# Grove-BLE_dual_model_v1_0.net
KiCad netlist of a schematic drawn in EAGLE
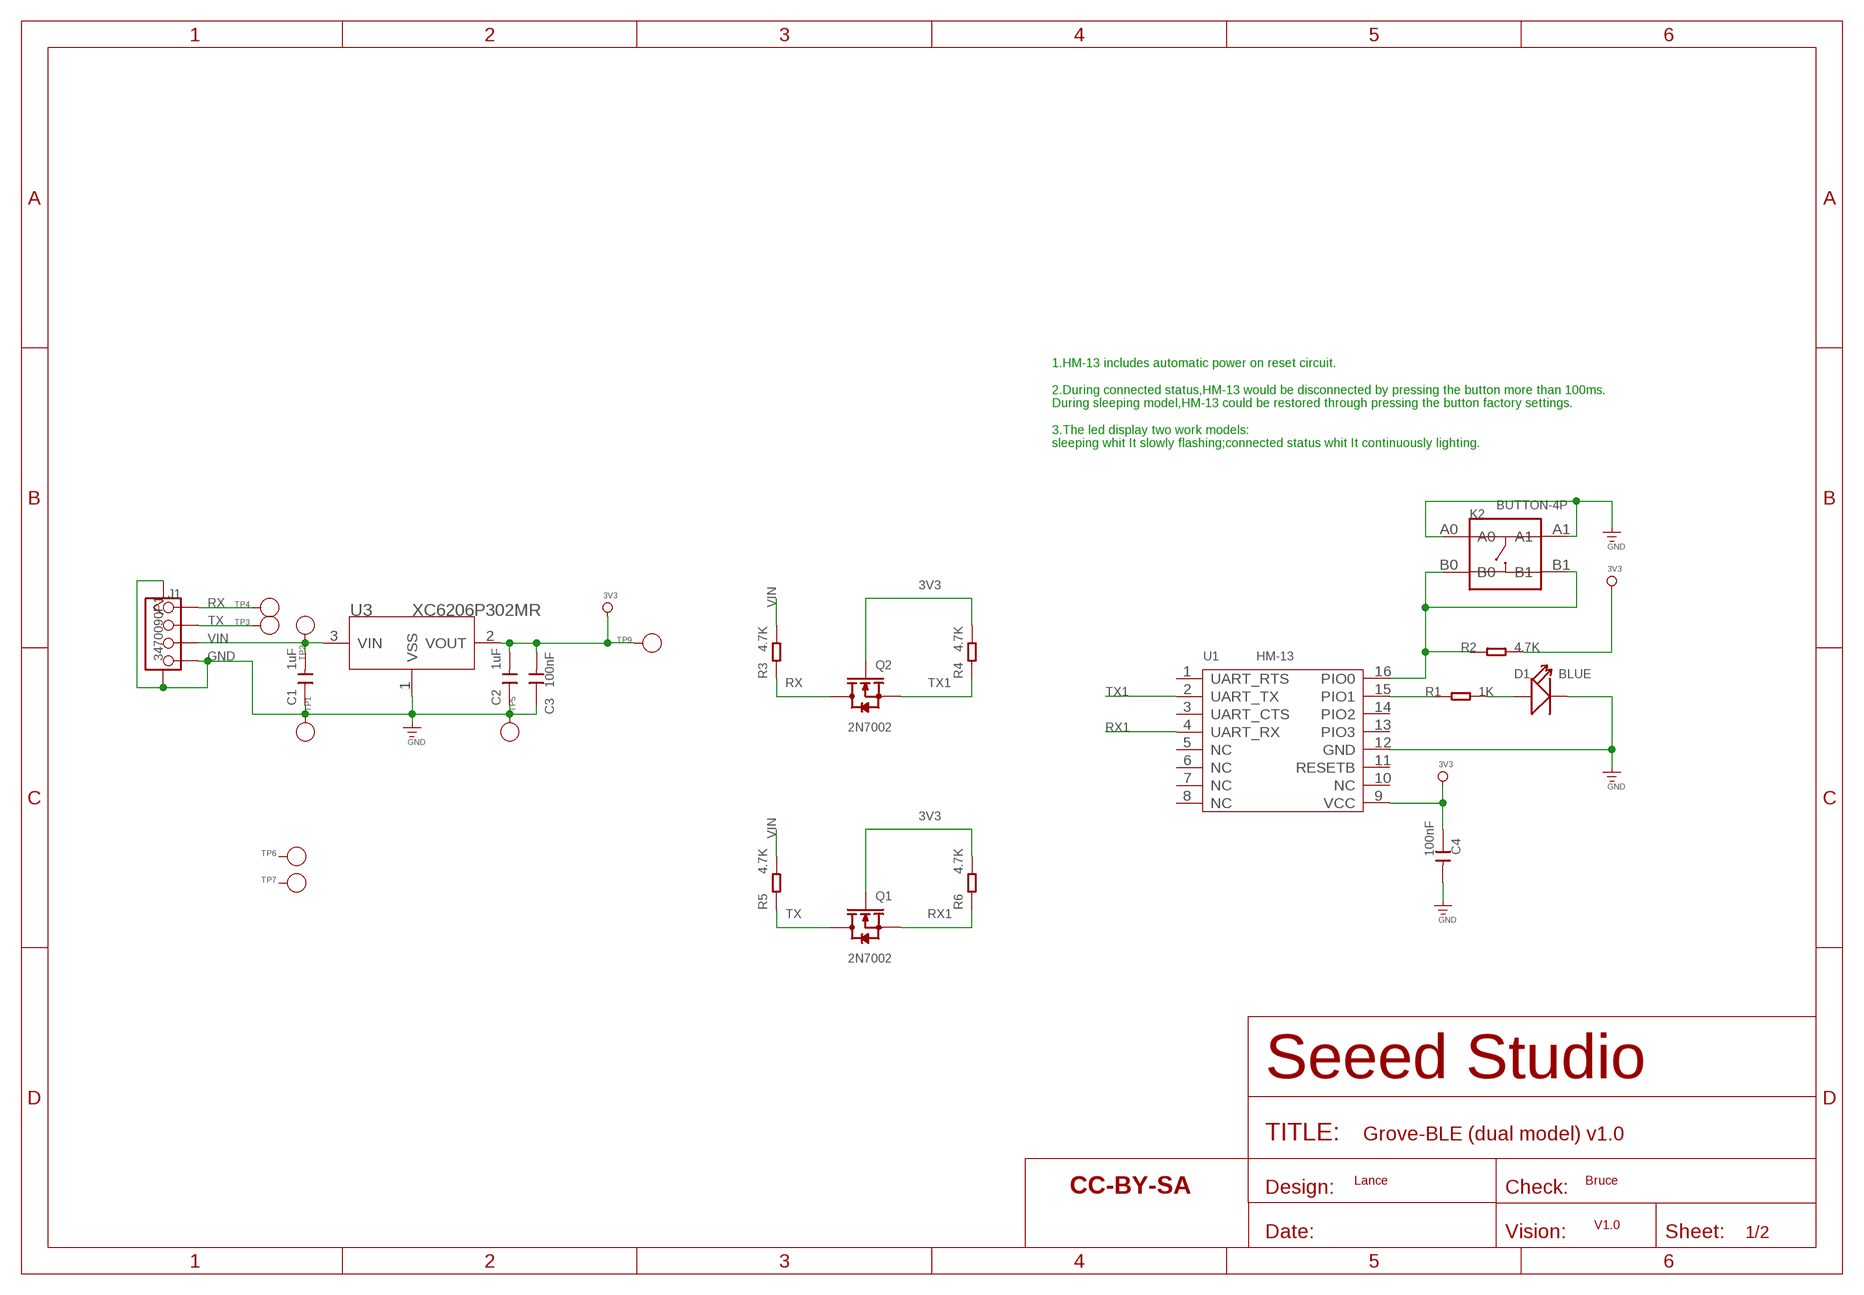
[diagram p0: schematic, sheet 1]
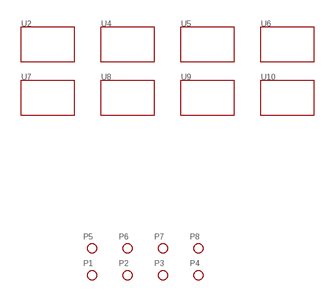
[diagram p1: schematic, sheet 2]

(export (version "E")
  (design (tool "Eeschema 10.0.6"))
  (components
    (comp (ref "C1")
      (value "1uF")
      (footprint "eagle-import:C0603")
      (libsource (lib "eagle-import") (part "C-0603"))
    )
    (comp (ref "C2")
      (value "1uF")
      (footprint "eagle-import:C0603")
      (libsource (lib "eagle-import") (part "C-0603"))
    )
    (comp (ref "C3")
      (value "100nF")
      (footprint "eagle-import:C0603")
      (libsource (lib "eagle-import") (part "C-0603"))
    )
    (comp (ref "C4")
      (value "100nF")
      (footprint "eagle-import:C0603")
      (libsource (lib "eagle-import") (part "C-0603"))
    )
    (comp (ref "D1")
      (value "BLUE")
      (footprint "eagle-import:LED-0603")
      (libsource (lib "eagle-import") (part "LED'0603'"))
    )
    (comp (ref "J1")
      (value "3470090P1")
      (footprint "eagle-import:4P-SMD-2.0")
      (libsource (lib "eagle-import") (part "TWIG-4P-2.0-SMD-FEMALE-REINFORCE'DD'"))
    )
    (comp (ref "K2")
      (value "BUTTON-4P")
      (footprint "eagle-import:4P-SMD-L3.35_W3.35_H1.5MM")
      (libsource (lib "eagle-import") (part "BUTTON-4P-3.3X3.3"))
    )
    (comp (ref "Q1")
      (value "2N7002")
      (footprint "eagle-import:SOT23")
      (libsource (lib "eagle-import") (part "MOSFET-N'SOT23'"))
    )
    (comp (ref "Q2")
      (value "2N7002")
      (footprint "eagle-import:SOT23")
      (libsource (lib "eagle-import") (part "MOSFET-N'SOT23'"))
    )
    (comp (ref "R1")
      (value "1K")
      (footprint "eagle-import:R0603")
      (libsource (lib "eagle-import") (part "R-0603"))
    )
    (comp (ref "R2")
      (value "4.7K")
      (footprint "eagle-import:R0603")
      (libsource (lib "eagle-import") (part "R-0603"))
    )
    (comp (ref "R3")
      (value "4.7K")
      (footprint "eagle-import:R0603")
      (libsource (lib "eagle-import") (part "R-0603"))
    )
    (comp (ref "R4")
      (value "4.7K")
      (footprint "eagle-import:R0603")
      (libsource (lib "eagle-import") (part "R-0603"))
    )
    (comp (ref "R5")
      (value "4.7K")
      (footprint "eagle-import:R0603")
      (libsource (lib "eagle-import") (part "R-0603"))
    )
    (comp (ref "R6")
      (value "4.7K")
      (footprint "eagle-import:R0603")
      (libsource (lib "eagle-import") (part "R-0603"))
    )
    (comp (ref "TP1")
      (value "GND")
      (footprint "eagle-import:TP_4545")
      (fields (field (name "PARTNO") "DNP"))
      (libsource (lib "eagle-import") (part "PAD-TEST-POINT'4545'"))
    )
    (comp (ref "TP2")
      (value "VIN")
      (footprint "eagle-import:TP_4545")
      (fields (field (name "PARTNO") "DNP"))
      (libsource (lib "eagle-import") (part "PAD-TEST-POINT'4545'"))
    )
    (comp (ref "TP3")
      (value "RX")
      (footprint "eagle-import:TP_4545")
      (fields (field (name "PARTNO") "DNP"))
      (libsource (lib "eagle-import") (part "PAD-TEST-POINT'4545'"))
    )
    (comp (ref "TP4")
      (value "TX")
      (footprint "eagle-import:TP_4545")
      (fields (field (name "PARTNO") "DNP"))
      (libsource (lib "eagle-import") (part "PAD-TEST-POINT'4545'"))
    )
    (comp (ref "TP5")
      (value "PAD-TEST-POINT'4545'")
      (footprint "eagle-import:TP_4545")
      (fields (field (name "PARTNO") "DNP"))
      (libsource (lib "eagle-import") (part "PAD-TEST-POINT'4545'"))
    )
    (comp (ref "TP6")
      (value "PAD-TEST-POINT'4545'")
      (footprint "eagle-import:TP_4545")
      (fields (field (name "PARTNO") "DNP"))
      (libsource (lib "eagle-import") (part "PAD-TEST-POINT'4545'"))
    )
    (comp (ref "TP7")
      (value "PAD-TEST-POINT'4545'")
      (footprint "eagle-import:TP_4545")
      (fields (field (name "PARTNO") "DNP"))
      (libsource (lib "eagle-import") (part "PAD-TEST-POINT'4545'"))
    )
    (comp (ref "TP9")
      (value "3V3")
      (footprint "eagle-import:TP_4545")
      (fields (field (name "PARTNO") "DNP"))
      (libsource (lib "eagle-import") (part "PAD-TEST-POINT'4545'"))
    )
    (comp (ref "U$1")
      (value "SEEEDSTUDIO-OPEN-SCH-FRAME")
      (footprint "eagle-import:SEEEDSTUDIO-PCB-FRAME")
      (libsource (lib "eagle-import") (part "SEEEDSTUDIO-OPEN-SCH-FRAME"))
    )
    (comp (ref "U1")
      (value "HM-13")
      (footprint "eagle-import:16P-L18.5_W13.5_H2.3MM")
      (libsource (lib "eagle-import") (part "MOUDLE-BLUETOOTH-HM-13"))
    )
    (comp (ref "U3")
      (value "XC6206P302MR")
      (footprint "eagle-import:SOT23")
      (libsource (lib "eagle-import") (part "XC6206MR"))
    )
    (comp (ref "P1")
      (value "PAD-MARK")
      (footprint "eagle-import:ROUND-MARK-1.0")
      (fields (field (name "PARTNO") "DNP"))
      (libsource (lib "eagle-import") (part "PAD-MARK"))
    )
    (comp (ref "P2")
      (value "PAD-MARK")
      (footprint "eagle-import:ROUND-MARK-1.0")
      (fields (field (name "PARTNO") "DNP"))
      (libsource (lib "eagle-import") (part "PAD-MARK"))
    )
    (comp (ref "P3")
      (value "PAD-MARK")
      (footprint "eagle-import:ROUND-MARK-1.0")
      (fields (field (name "PARTNO") "DNP"))
      (libsource (lib "eagle-import") (part "PAD-MARK"))
    )
    (comp (ref "P4")
      (value "PAD-MARK")
      (footprint "eagle-import:ROUND-MARK-1.0")
      (fields (field (name "PARTNO") "DNP"))
      (libsource (lib "eagle-import") (part "PAD-MARK"))
    )
    (comp (ref "P5")
      (value "PAD-MARK")
      (footprint "eagle-import:ROUND-MARK-1.0")
      (fields (field (name "PARTNO") "DNP"))
      (libsource (lib "eagle-import") (part "PAD-MARK"))
    )
    (comp (ref "P6")
      (value "PAD-MARK")
      (footprint "eagle-import:ROUND-MARK-1.0")
      (fields (field (name "PARTNO") "DNP"))
      (libsource (lib "eagle-import") (part "PAD-MARK"))
    )
    (comp (ref "P7")
      (value "PAD-MARK")
      (footprint "eagle-import:ROUND-MARK-1.0")
      (fields (field (name "PARTNO") "DNP"))
      (libsource (lib "eagle-import") (part "PAD-MARK"))
    )
    (comp (ref "P8")
      (value "PAD-MARK")
      (footprint "eagle-import:ROUND-MARK-1.0")
      (fields (field (name "PARTNO") "DNP"))
      (libsource (lib "eagle-import") (part "PAD-MARK"))
    )
    (comp (ref "U2")
      (value "TWIG'2U'")
      (footprint "eagle-import:GROVE-TEST-PLATFORM")
      (libsource (lib "eagle-import") (part "TWIG'2U'"))
    )
    (comp (ref "U4")
      (value "TWIG'2U'")
      (footprint "eagle-import:GROVE-TEST-PLATFORM")
      (libsource (lib "eagle-import") (part "TWIG'2U'"))
    )
    (comp (ref "U5")
      (value "TWIG'2U'")
      (footprint "eagle-import:GROVE-TEST-PLATFORM")
      (libsource (lib "eagle-import") (part "TWIG'2U'"))
    )
    (comp (ref "U6")
      (value "TWIG'2U'")
      (footprint "eagle-import:GROVE-TEST-PLATFORM")
      (libsource (lib "eagle-import") (part "TWIG'2U'"))
    )
    (comp (ref "U7")
      (value "TWIG'2U'")
      (footprint "eagle-import:GROVE-TEST-PLATFORM")
      (libsource (lib "eagle-import") (part "TWIG'2U'"))
    )
    (comp (ref "U8")
      (value "TWIG'2U'")
      (footprint "eagle-import:GROVE-TEST-PLATFORM")
      (libsource (lib "eagle-import") (part "TWIG'2U'"))
    )
    (comp (ref "U9")
      (value "TWIG'2U'")
      (footprint "eagle-import:GROVE-TEST-PLATFORM")
      (libsource (lib "eagle-import") (part "TWIG'2U'"))
    )
    (comp (ref "U10")
      (value "TWIG'2U'")
      (footprint "eagle-import:GROVE-TEST-PLATFORM")
      (libsource (lib "eagle-import") (part "TWIG'2U'"))
    )
  )
  (nets
    (net (code "1") (name "3V3") (class "Default")
      (node (ref "C2") (pin "2") (pinfunction "2_2") (pintype "passive"))
      (node (ref "C3") (pin "2") (pinfunction "2_2") (pintype "passive"))
      (node (ref "C4") (pin "1") (pinfunction "1_1") (pintype "passive"))
      (node (ref "Q1") (pin "1") (pinfunction "G_1") (pintype "passive"))
      (node (ref "Q2") (pin "1") (pinfunction "G_1") (pintype "passive"))
      (node (ref "R2") (pin "2") (pinfunction "2_2") (pintype "passive"))
      (node (ref "R4") (pin "2") (pinfunction "2_2") (pintype "passive"))
      (node (ref "R6") (pin "2") (pinfunction "2_2") (pintype "passive"))
      (node (ref "TP9") (pin "T") (pinfunction "T_T") (pintype "bidirectional"))
      (node (ref "U1") (pin "9") (pinfunction "VCC_9") (pintype "bidirectional"))
      (node (ref "U3") (pin "2") (pinfunction "VOUT_2") (pintype "output"))
    )
    (net (code "2") (name "GND") (class "Default")
      (node (ref "C1") (pin "1") (pinfunction "1_1") (pintype "passive"))
      (node (ref "C2") (pin "1") (pinfunction "1_1") (pintype "passive"))
      (node (ref "C3") (pin "1") (pinfunction "1_1") (pintype "passive"))
      (node (ref "C4") (pin "2") (pinfunction "2_2") (pintype "passive"))
      (node (ref "D1") (pin "-") (pinfunction "-_-") (pintype "passive"))
      (node (ref "J1") (pin "4") (pinfunction "4_4") (pintype "bidirectional"))
      (node (ref "J1") (pin "SS1") (pinfunction "SS1_SS1") (pintype "bidirectional"))
      (node (ref "J1") (pin "SS2") (pinfunction "SS2_SS2") (pintype "bidirectional"))
      (node (ref "K2") (pin "A0") (pinfunction "A0_A0") (pintype "bidirectional"))
      (node (ref "K2") (pin "A1") (pinfunction "A1_A1") (pintype "bidirectional"))
      (node (ref "TP1") (pin "T") (pinfunction "T_T") (pintype "bidirectional"))
      (node (ref "TP5") (pin "T") (pinfunction "T_T") (pintype "bidirectional"))
      (node (ref "U1") (pin "12") (pinfunction "GND_12") (pintype "bidirectional"))
      (node (ref "U3") (pin "1") (pinfunction "VSS_1") (pintype "power_in"))
    )
    (net (code "3") (name "Net-(D1-Pad+)") (class "Default")
      (node (ref "D1") (pin "+") (pinfunction "+_+") (pintype "passive"))
      (node (ref "R1") (pin "2") (pinfunction "2_2") (pintype "passive"))
    )
    (net (code "4") (name "Net-(U1-PIO0)") (class "Default")
      (node (ref "K2") (pin "B0") (pinfunction "B0_B0") (pintype "bidirectional"))
      (node (ref "K2") (pin "B1") (pinfunction "B1_B1") (pintype "bidirectional"))
      (node (ref "R2") (pin "1") (pinfunction "1_1") (pintype "passive"))
      (node (ref "U1") (pin "16") (pinfunction "PIO0_16") (pintype "bidirectional"))
    )
    (net (code "5") (name "Net-(U1-PIO1)") (class "Default")
      (node (ref "R1") (pin "1") (pinfunction "1_1") (pintype "passive"))
      (node (ref "U1") (pin "15") (pinfunction "PIO1_15") (pintype "bidirectional"))
    )
    (net (code "6") (name "RX") (class "Default")
      (node (ref "J1") (pin "1") (pinfunction "1_1") (pintype "bidirectional"))
      (node (ref "Q2") (pin "3") (pinfunction "D_3") (pintype "passive"))
      (node (ref "R3") (pin "1") (pinfunction "1_1") (pintype "passive"))
      (node (ref "TP4") (pin "T") (pinfunction "T_T") (pintype "bidirectional"))
    )
    (net (code "7") (name "RX1") (class "Default")
      (node (ref "Q1") (pin "2") (pinfunction "S_2") (pintype "passive"))
      (node (ref "R6") (pin "1") (pinfunction "1_1") (pintype "passive"))
      (node (ref "U1") (pin "4") (pinfunction "UART_RX_4") (pintype "bidirectional"))
    )
    (net (code "8") (name "TX") (class "Default")
      (node (ref "J1") (pin "2") (pinfunction "2_2") (pintype "bidirectional"))
      (node (ref "Q1") (pin "3") (pinfunction "D_3") (pintype "passive"))
      (node (ref "R5") (pin "1") (pinfunction "1_1") (pintype "passive"))
      (node (ref "TP3") (pin "T") (pinfunction "T_T") (pintype "bidirectional"))
    )
    (net (code "9") (name "TX1") (class "Default")
      (node (ref "Q2") (pin "2") (pinfunction "S_2") (pintype "passive"))
      (node (ref "R4") (pin "1") (pinfunction "1_1") (pintype "passive"))
      (node (ref "U1") (pin "2") (pinfunction "UART_TX_2") (pintype "bidirectional"))
    )
    (net (code "10") (name "VIN") (class "Default")
      (node (ref "C1") (pin "2") (pinfunction "2_2") (pintype "passive"))
      (node (ref "J1") (pin "3") (pinfunction "3_3") (pintype "bidirectional"))
      (node (ref "R3") (pin "2") (pinfunction "2_2") (pintype "passive"))
      (node (ref "R5") (pin "2") (pinfunction "2_2") (pintype "passive"))
      (node (ref "TP2") (pin "T") (pinfunction "T_T") (pintype "bidirectional"))
      (node (ref "U3") (pin "3") (pinfunction "VIN_3") (pintype "input"))
    )
    (net (code "11") (name "unconnected-(TP6-PadT)") (class "Default")
      (node (ref "TP6") (pin "T") (pinfunction "T_T") (pintype "bidirectional"))
    )
    (net (code "12") (name "unconnected-(TP7-PadT)") (class "Default")
      (node (ref "TP7") (pin "T") (pinfunction "T_T") (pintype "bidirectional"))
    )
    (net (code "13") (name "unconnected-(U1-NC-Pad5)") (class "Default")
      (node (ref "U1") (pin "5") (pinfunction "NC_5") (pintype "bidirectional"))
    )
    (net (code "14") (name "unconnected-(U1-NC-Pad6)") (class "Default")
      (node (ref "U1") (pin "6") (pinfunction "NC_6") (pintype "bidirectional"))
    )
    (net (code "15") (name "unconnected-(U1-NC-Pad7)") (class "Default")
      (node (ref "U1") (pin "7") (pinfunction "NC_7") (pintype "bidirectional"))
    )
    (net (code "16") (name "unconnected-(U1-NC-Pad8)") (class "Default")
      (node (ref "U1") (pin "8") (pinfunction "NC_8") (pintype "bidirectional"))
    )
    (net (code "17") (name "unconnected-(U1-NC-Pad10)") (class "Default")
      (node (ref "U1") (pin "10") (pinfunction "NC_10") (pintype "bidirectional"))
    )
    (net (code "18") (name "unconnected-(U1-PIO2-Pad14)") (class "Default")
      (node (ref "U1") (pin "14") (pinfunction "PIO2_14") (pintype "bidirectional"))
    )
    (net (code "19") (name "unconnected-(U1-PIO3-Pad13)") (class "Default")
      (node (ref "U1") (pin "13") (pinfunction "PIO3_13") (pintype "bidirectional"))
    )
    (net (code "20") (name "unconnected-(U1-RESETB-Pad11)") (class "Default")
      (node (ref "U1") (pin "11") (pinfunction "RESETB_11") (pintype "bidirectional"))
    )
    (net (code "21") (name "unconnected-(U1-UART_CTS-Pad3)") (class "Default")
      (node (ref "U1") (pin "3") (pinfunction "UART_CTS_3") (pintype "bidirectional"))
    )
    (net (code "22") (name "unconnected-(U1-UART_RTS-Pad1)") (class "Default")
      (node (ref "U1") (pin "1") (pinfunction "UART_RTS_1") (pintype "bidirectional"))
    )
  )
)
